# example_schematic_5V.net
KiCad netlist of a schematic drawn in EAGLE
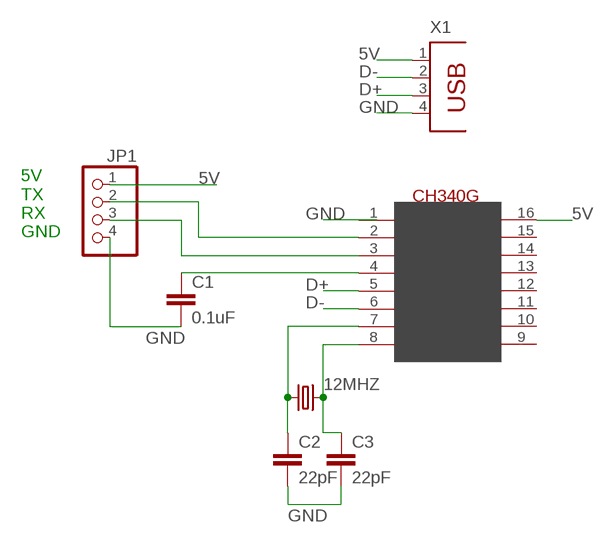
[diagram p0: schematic, sheet 1]

(export (version "E")
  (design (tool "Eeschema 10.0.6"))
  (components
    (comp (ref "12MHZ")
      (value "CRYSTALHC18U-V")
      (footprint "eagle-import:HC18U-V")
      (libsource (lib "eagle-import") (part "CRYSTALHC18U-V"))
    )
    (comp (ref "C1")
      (value "0.1uF")
      (footprint "eagle-import:C2.5-2")
      (libsource (lib "eagle-import") (part "C2.5/2"))
    )
    (comp (ref "C2")
      (value "22pF")
      (footprint "eagle-import:C2.5-2")
      (libsource (lib "eagle-import") (part "C2.5/2"))
    )
    (comp (ref "C3")
      (value "22pF")
      (footprint "eagle-import:C2.5-2")
      (libsource (lib "eagle-import") (part "C2.5/2"))
    )
    (comp (ref "JP1")
      (value "PINHD-1X4")
      (footprint "eagle-import:1X04")
      (libsource (lib "eagle-import") (part "PINHD-1X4"))
    )
    (comp (ref "U$1")
      (value "CH340G")
      (footprint "eagle-import:SOIC16")
      (libsource (lib "eagle-import") (part "CH340G"))
    )
    (comp (ref "X1")
      (value "PN61729")
      (footprint "eagle-import:PN61729")
      (libsource (lib "eagle-import") (part "PN61729"))
    )
  )
  (nets
    (net (code "1") (name "/5V") (class "Default")
      (node (ref "JP1") (pin "1") (pinfunction "1_1") (pintype "passive"))
      (node (ref "U$1") (pin "16") (pinfunction "VCC_16") (pintype "bidirectional"))
      (node (ref "X1") (pin "1") (pinfunction "1_1") (pintype "passive"))
    )
    (net (code "2") (name "/D+") (class "Default")
      (node (ref "U$1") (pin "5") (pinfunction "D+_5") (pintype "bidirectional"))
      (node (ref "X1") (pin "3") (pinfunction "3_3") (pintype "passive"))
    )
    (net (code "3") (name "/D-") (class "Default")
      (node (ref "U$1") (pin "6") (pinfunction "D-_6") (pintype "bidirectional"))
      (node (ref "X1") (pin "2") (pinfunction "2_2") (pintype "passive"))
    )
    (net (code "4") (name "/GND") (class "Default")
      (node (ref "C1") (pin "2") (pinfunction "2_2") (pintype "passive"))
      (node (ref "C2") (pin "2") (pinfunction "2_2") (pintype "passive"))
      (node (ref "C3") (pin "2") (pinfunction "2_2") (pintype "passive"))
      (node (ref "JP1") (pin "4") (pinfunction "4_4") (pintype "passive"))
      (node (ref "X1") (pin "4") (pinfunction "4_4") (pintype "passive"))
    )
    (net (code "5") (name "Net-(U$1-RX)") (class "Default")
      (node (ref "JP1") (pin "3") (pinfunction "3_3") (pintype "passive"))
      (node (ref "U$1") (pin "3") (pinfunction "RX_3") (pintype "bidirectional"))
    )
    (net (code "6") (name "Net-(U$1-TX)") (class "Default")
      (node (ref "JP1") (pin "2") (pinfunction "2_2") (pintype "passive"))
      (node (ref "U$1") (pin "2") (pinfunction "TX_2") (pintype "bidirectional"))
    )
    (net (code "7") (name "Net-(U$1-V3)") (class "Default")
      (node (ref "C1") (pin "1") (pinfunction "1_1") (pintype "passive"))
      (node (ref "U$1") (pin "4") (pinfunction "V3_4") (pintype "bidirectional"))
    )
    (net (code "8") (name "Net-(U$1-XI)") (class "Default")
      (node (ref "12MHZ") (pin "1") (pinfunction "1_1") (pintype "passive"))
      (node (ref "C2") (pin "1") (pinfunction "1_1") (pintype "passive"))
      (node (ref "U$1") (pin "7") (pinfunction "XI_7") (pintype "bidirectional"))
    )
    (net (code "9") (name "Net-(U$1-XO)") (class "Default")
      (node (ref "12MHZ") (pin "2") (pinfunction "2_2") (pintype "passive"))
      (node (ref "C3") (pin "1") (pinfunction "1_1") (pintype "passive"))
      (node (ref "U$1") (pin "8") (pinfunction "XO_8") (pintype "bidirectional"))
    )
    (net (code "10") (name "unconnected-(U$1-CTS-Pad9)") (class "Default")
      (node (ref "U$1") (pin "9") (pinfunction "CTS_9") (pintype "bidirectional"))
    )
    (net (code "11") (name "unconnected-(U$1-DCD-Pad12)") (class "Default")
      (node (ref "U$1") (pin "12") (pinfunction "DCD_12") (pintype "bidirectional"))
    )
    (net (code "12") (name "unconnected-(U$1-DSR-Pad10)") (class "Default")
      (node (ref "U$1") (pin "10") (pinfunction "DSR_10") (pintype "bidirectional"))
    )
    (net (code "13") (name "unconnected-(U$1-DTR-Pad13)") (class "Default")
      (node (ref "U$1") (pin "13") (pinfunction "DTR_13") (pintype "bidirectional"))
    )
    (net (code "14") (name "unconnected-(U$1-GND-Pad1)") (class "Default")
      (node (ref "U$1") (pin "1") (pinfunction "GND_1") (pintype "bidirectional"))
    )
    (net (code "15") (name "unconnected-(U$1-RI-Pad11)") (class "Default")
      (node (ref "U$1") (pin "11") (pinfunction "RI_11") (pintype "bidirectional"))
    )
    (net (code "16") (name "unconnected-(U$1-RS232-Pad15)") (class "Default")
      (node (ref "U$1") (pin "15") (pinfunction "RS232_15") (pintype "bidirectional"))
    )
    (net (code "17") (name "unconnected-(U$1-RTS-Pad14)") (class "Default")
      (node (ref "U$1") (pin "14") (pinfunction "RTS_14") (pintype "bidirectional"))
    )
  )
)
